# Empel_PCB_Boost_AJ.net
KiCad netlist of a schematic drawn in EasyEDA Pro
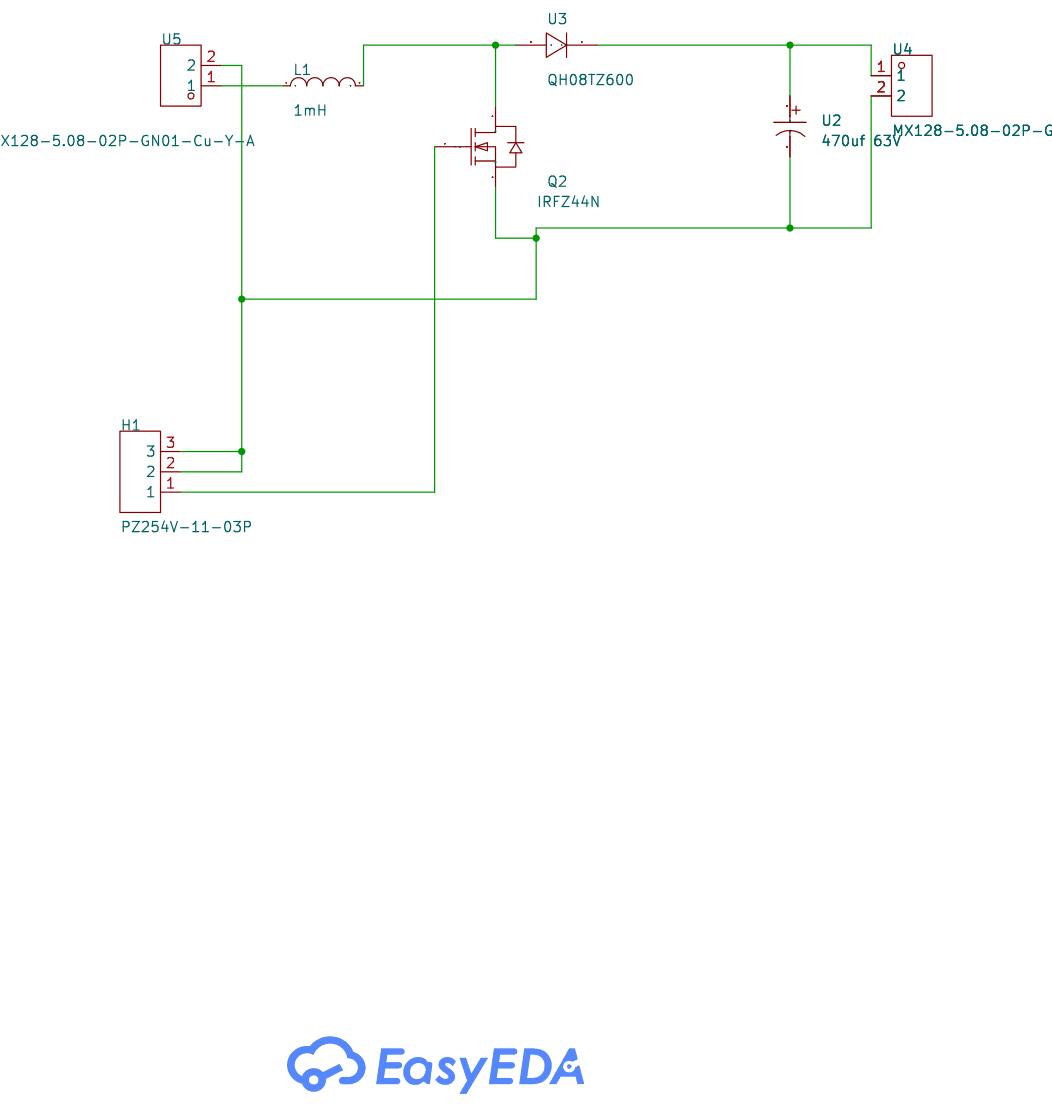
[diagram p0: schematic sheet]

(export (version "E")
  (design (tool "Eeschema 10.0.6"))
  (components
    (comp (ref "H1")
      (value "PZ254V-11-03P")
      (footprint "easyedapro:HDR-TH_3P-P2.54-V-M")
      (fields (field (name "Manufacturer") "XFCN(兴飞)"))
      (libsource (lib "easyedapro") (part "PZ254V-11-03P_C2937625"))
    )
    (comp (ref "L1")
      (value "1mH")
      (footprint "easyedapro:IND-TH_BD32.5-P29.0-D0.7_2324-H-RC")
      (fields (field (name "Manufacturer Part") "2324-H-RC") (field (name "Manufacturer") "BOURNS"))
      (libsource (lib "easyedapro") (part "2324-H-RC"))
    )
    (comp (ref "Q2")
      (value "IRFZ44N")
      (footprint "easyedapro:TO-220-3_L9.9-W4.5-P2.54-L")
      (fields (field (name "Manufacturer") "minos(迈诺斯)"))
      (libsource (lib "easyedapro") (part "IRFZ44N"))
    )
    (comp (ref "U2")
      (value "470uf 63V")
      (footprint "easyedapro:CAP-TH_BD12.5-P5.00-D0.6-FD")
      (libsource (lib "easyedapro") (part "470UF 63V"))
    )
    (comp (ref "U3")
      (value "QH08TZ600")
      (footprint "easyedapro:TO-220AC_L10.0-W4.5-P5.08-L")
      (fields (field (name "Manufacturer") "Power Integrations(帕沃英蒂格盛)"))
      (libsource (lib "easyedapro") (part "QH08TZ600"))
    )
    (comp (ref "U4")
      (value "MX128-5.08-02P-GN01-Cu-Y-A")
      (footprint "easyedapro:CONN-TH_2P-P5.08_MX128-5.08-GN01-02P-CU-Y-A")
      (fields (field (name "Manufacturer") "MAX(迈旭)"))
      (libsource (lib "easyedapro") (part "MX128-5.08-02P-GN01-CU-Y-A"))
    )
    (comp (ref "U5")
      (value "MX128-5.08-02P-GN01-Cu-Y-A")
      (footprint "easyedapro:CONN-TH_2P-P5.08_MX128-5.08-GN01-02P-CU-Y-A")
      (fields (field (name "Manufacturer") "MAX(迈旭)"))
      (libsource (lib "easyedapro") (part "MX128-5.08-02P-GN01-CU-Y-A"))
    )
  )
  (nets
    (net (code "1") (name "Net-(L1-Pad1)") (class "Default")
      (node (ref "L1") (pin "1") (pinfunction "1_1") (pintype "unspecified"))
      (node (ref "U5") (pin "1") (pinfunction "1_1") (pintype "unspecified"))
    )
    (net (code "2") (name "Net-(Q2-D)") (class "Default")
      (node (ref "L1") (pin "2") (pinfunction "2_2") (pintype "unspecified"))
      (node (ref "Q2") (pin "2") (pinfunction "D_2") (pintype "unspecified"))
      (node (ref "U3") (pin "2") (pinfunction "A_2") (pintype "unspecified"))
    )
    (net (code "3") (name "Net-(Q2-G)") (class "Default")
      (node (ref "H1") (pin "1") (pinfunction "1_1") (pintype "unspecified"))
      (node (ref "Q2") (pin "1") (pinfunction "G_1") (pintype "unspecified"))
    )
    (net (code "4") (name "Net-(Q2-S)") (class "Default")
      (node (ref "H1") (pin "2") (pinfunction "2_2") (pintype "unspecified"))
      (node (ref "H1") (pin "3") (pinfunction "3_3") (pintype "unspecified"))
      (node (ref "Q2") (pin "3") (pinfunction "S_3") (pintype "unspecified"))
      (node (ref "U2") (pin "2") (pinfunction "2_2") (pintype "input"))
      (node (ref "U4") (pin "2") (pinfunction "2_2") (pintype "unspecified"))
      (node (ref "U5") (pin "2") (pinfunction "2_2") (pintype "unspecified"))
    )
    (net (code "5") (name "Net-(U3-K)") (class "Default")
      (node (ref "U2") (pin "1") (pinfunction "1_1") (pintype "input"))
      (node (ref "U3") (pin "1") (pinfunction "K_1") (pintype "unspecified"))
      (node (ref "U4") (pin "1") (pinfunction "1_1") (pintype "unspecified"))
    )
  )
)
